# RPi_Extension_load_w_ready.net
KiCad netlist of a schematic drawn in EAGLE
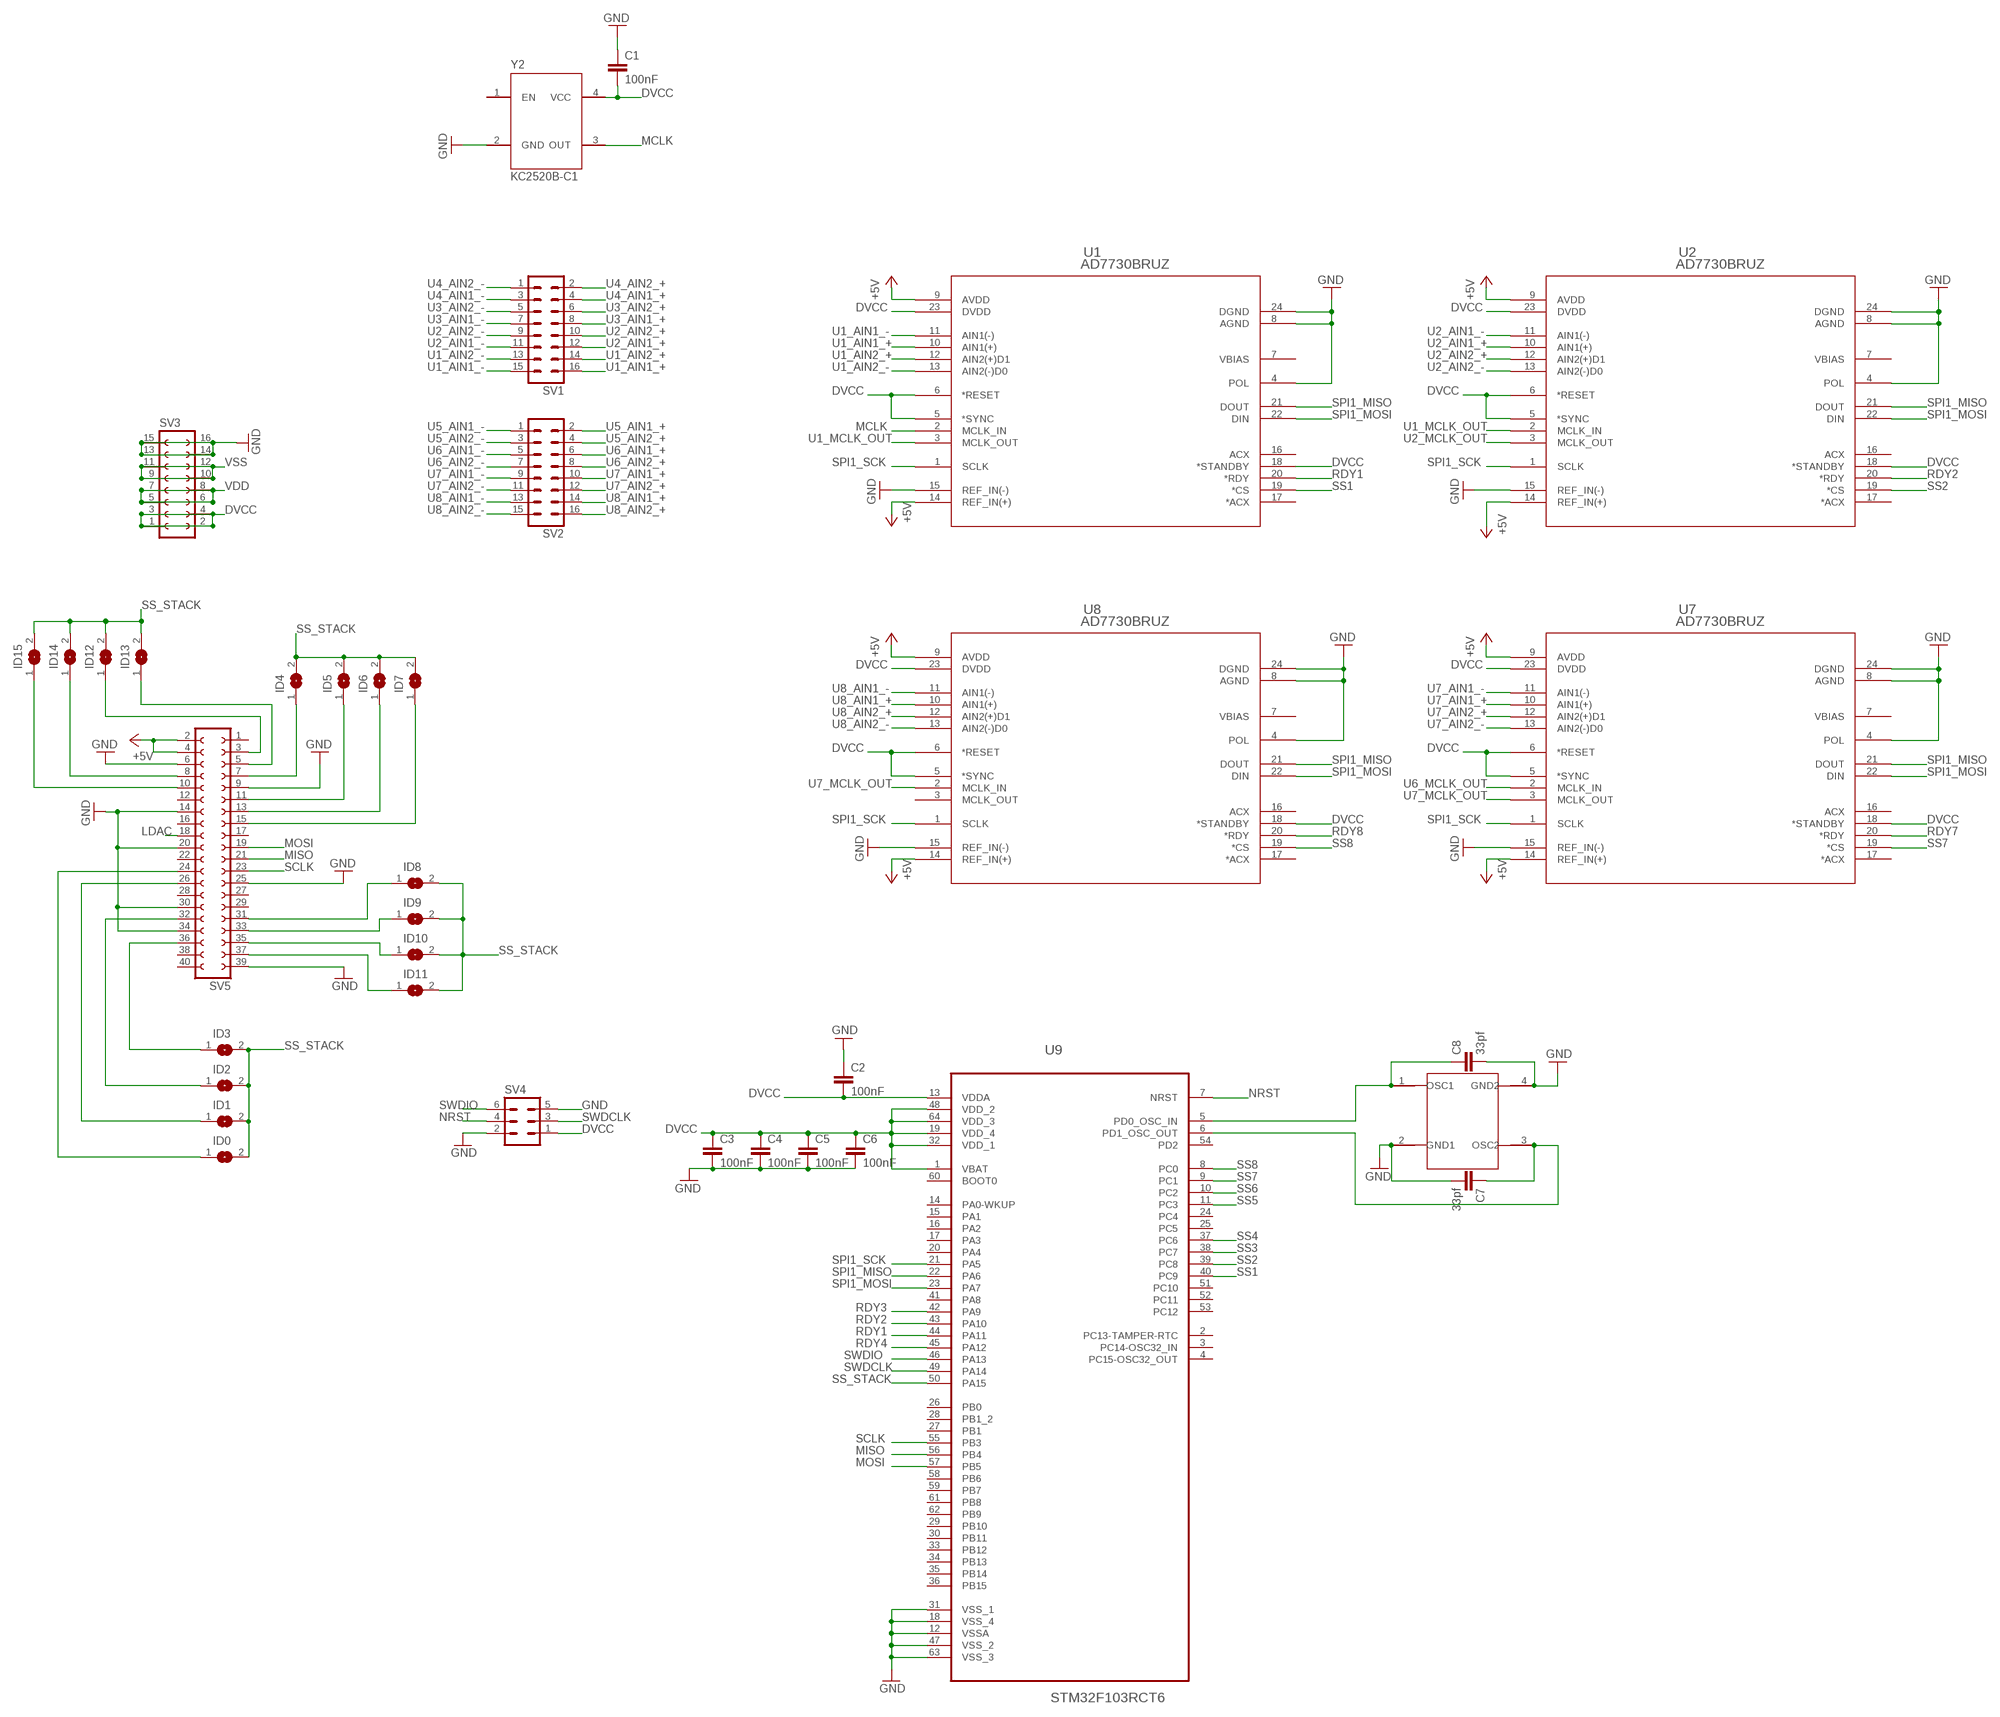
[diagram p0: schematic, sheet 1, part 1 of 2]
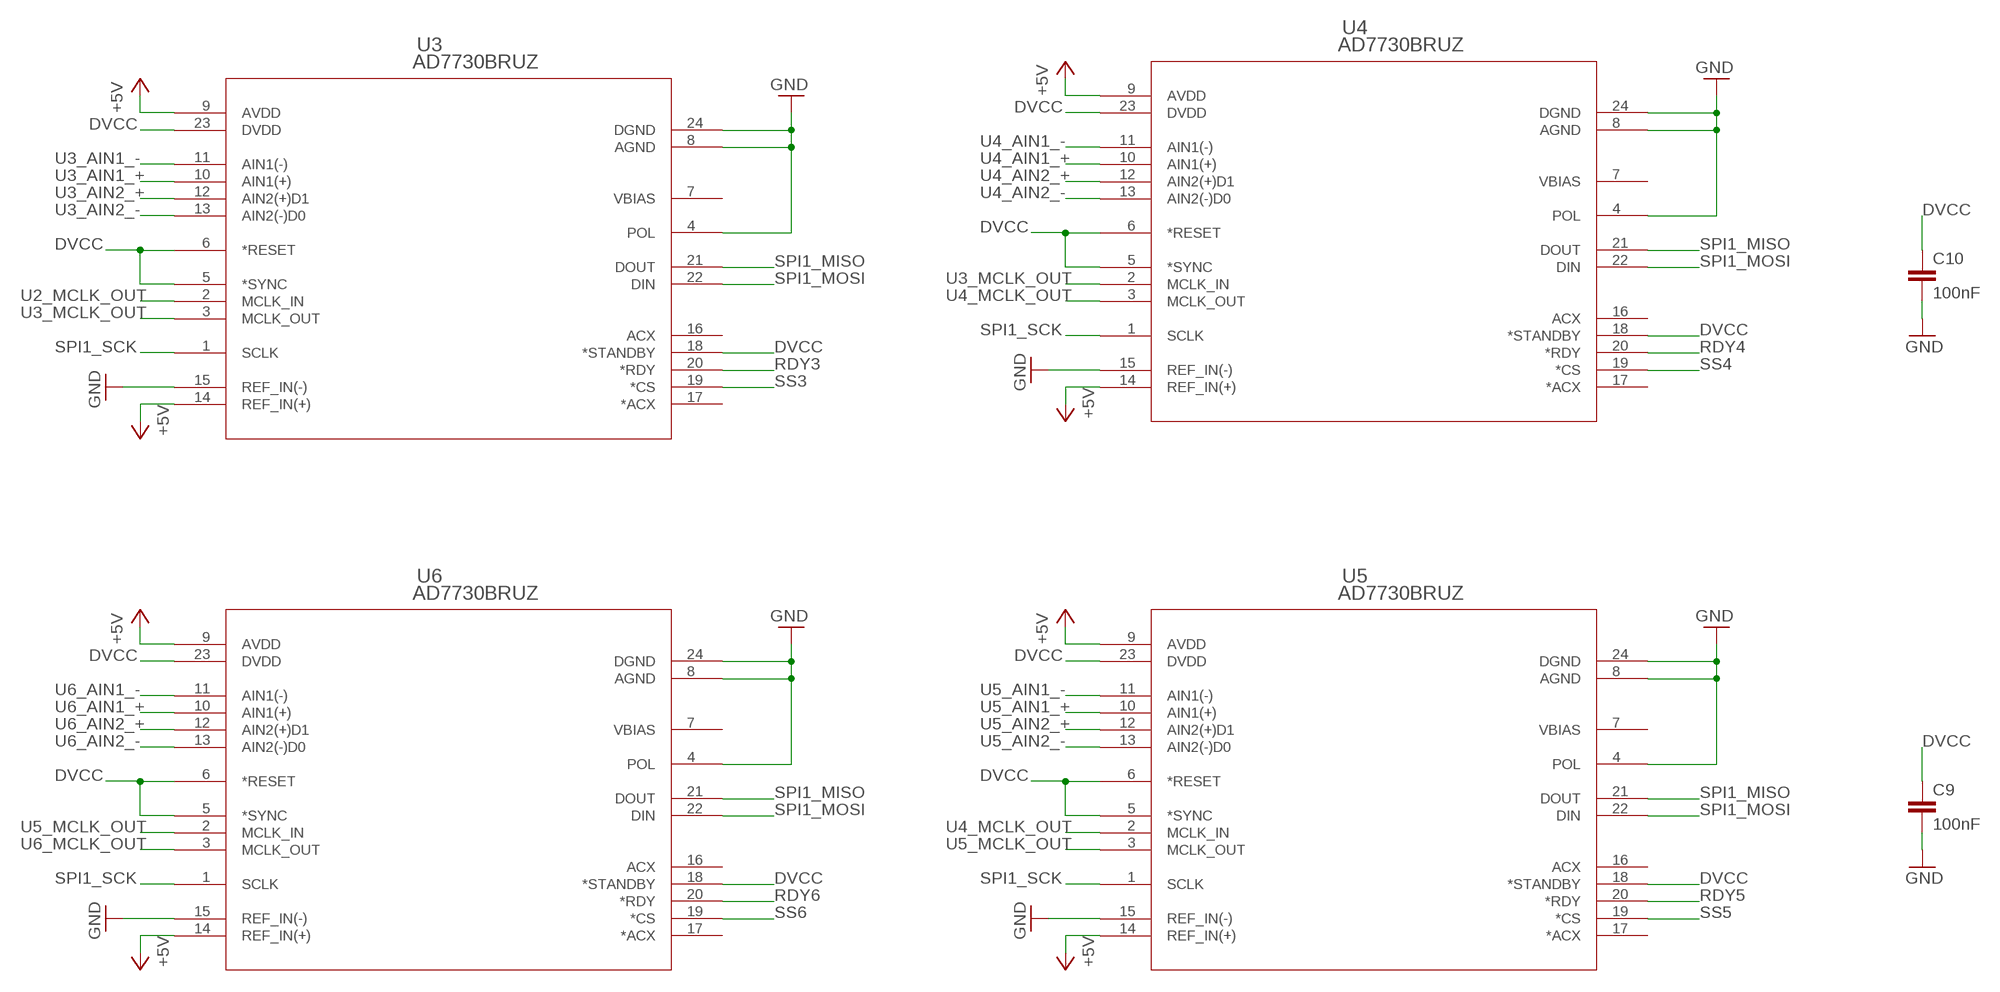
[diagram p1: schematic, sheet 1, part 2 of 2]

(export (version "E")
  (design (tool "Eeschema 10.0.6"))
  (components
    (comp (ref "C1")
      (value "100nF")
      (footprint "eagle-import:C0603")
      (libsource (lib "eagle-import") (part "C-EUC0603"))
    )
    (comp (ref "C2")
      (value "100nF")
      (footprint "eagle-import:C0603")
      (libsource (lib "eagle-import") (part "C-EUC0603"))
    )
    (comp (ref "C3")
      (value "100nF")
      (footprint "eagle-import:C0603")
      (libsource (lib "eagle-import") (part "C-EUC0603"))
    )
    (comp (ref "C4")
      (value "100nF")
      (footprint "eagle-import:C0603")
      (libsource (lib "eagle-import") (part "C-EUC0603"))
    )
    (comp (ref "C5")
      (value "100nF")
      (footprint "eagle-import:C0603")
      (libsource (lib "eagle-import") (part "C-EUC0603"))
    )
    (comp (ref "C6")
      (value "100nF")
      (footprint "eagle-import:C0603")
      (libsource (lib "eagle-import") (part "C-EUC0603"))
    )
    (comp (ref "C7")
      (value "33pf")
      (footprint "eagle-import:C0603")
      (libsource (lib "eagle-import") (part "C-EUC0603"))
    )
    (comp (ref "C8")
      (value "33pf")
      (footprint "eagle-import:C0603")
      (libsource (lib "eagle-import") (part "C-EUC0603"))
    )
    (comp (ref "C9")
      (value "100nF")
      (footprint "eagle-import:C0603")
      (libsource (lib "eagle-import") (part "C-EUC0603"))
    )
    (comp (ref "C10")
      (value "100nF")
      (footprint "eagle-import:C0603")
      (libsource (lib "eagle-import") (part "C-EUC0603"))
    )
    (comp (ref "ID0") (value "SJ") (footprint "eagle-import:SJ") (libsource (lib "eagle-import") (part "SJ")))
    (comp (ref "ID1") (value "SJ") (footprint "eagle-import:SJ") (libsource (lib "eagle-import") (part "SJ")))
    (comp (ref "ID2") (value "SJ") (footprint "eagle-import:SJ") (libsource (lib "eagle-import") (part "SJ")))
    (comp (ref "ID3") (value "SJ") (footprint "eagle-import:SJ") (libsource (lib "eagle-import") (part "SJ")))
    (comp (ref "ID4") (value "SJ") (footprint "eagle-import:SJ") (libsource (lib "eagle-import") (part "SJ")))
    (comp (ref "ID5") (value "SJ") (footprint "eagle-import:SJ") (libsource (lib "eagle-import") (part "SJ")))
    (comp (ref "ID6") (value "SJ") (footprint "eagle-import:SJ") (libsource (lib "eagle-import") (part "SJ")))
    (comp (ref "ID7") (value "SJ") (footprint "eagle-import:SJ") (libsource (lib "eagle-import") (part "SJ")))
    (comp (ref "ID8") (value "SJ") (footprint "eagle-import:SJ") (libsource (lib "eagle-import") (part "SJ")))
    (comp (ref "ID9") (value "SJ") (footprint "eagle-import:SJ") (libsource (lib "eagle-import") (part "SJ")))
    (comp (ref "ID10")
      (value "SJ")
      (footprint "eagle-import:SJ")
      (libsource (lib "eagle-import") (part "SJ"))
    )
    (comp (ref "ID11")
      (value "SJ")
      (footprint "eagle-import:SJ")
      (libsource (lib "eagle-import") (part "SJ"))
    )
    (comp (ref "ID12")
      (value "SJ")
      (footprint "eagle-import:SJ")
      (libsource (lib "eagle-import") (part "SJ"))
    )
    (comp (ref "ID13")
      (value "SJ")
      (footprint "eagle-import:SJ")
      (libsource (lib "eagle-import") (part "SJ"))
    )
    (comp (ref "ID14")
      (value "SJ")
      (footprint "eagle-import:SJ")
      (libsource (lib "eagle-import") (part "SJ"))
    )
    (comp (ref "ID15")
      (value "SJ")
      (footprint "eagle-import:SJ")
      (libsource (lib "eagle-import") (part "SJ"))
    )
    (comp (ref "SV1")
      (value "MA08-2W")
      (footprint "eagle-import:MA08-2W")
      (libsource (lib "eagle-import") (part "MA08-2W"))
    )
    (comp (ref "SV2")
      (value "MA08-2W")
      (footprint "eagle-import:MA08-2W")
      (libsource (lib "eagle-import") (part "MA08-2W"))
    )
    (comp (ref "SV3")
      (value "FE08-2")
      (footprint "eagle-import:FE08-2")
      (libsource (lib "eagle-import") (part "FE08-2"))
    )
    (comp (ref "SV4")
      (value "MA03-2")
      (footprint "eagle-import:MA03-2")
      (libsource (lib "eagle-import") (part "MA03-2"))
    )
    (comp (ref "SV5")
      (value "FE20-2")
      (footprint "eagle-import:FE20-2")
      (libsource (lib "eagle-import") (part "FE20-2"))
    )
    (comp (ref "U1")
      (value "AD7730BRUZ")
      (footprint "eagle-import:RU_24")
      (libsource (lib "eagle-import") (part "AD7730BRUZ"))
    )
    (comp (ref "U2")
      (value "AD7730BRUZ")
      (footprint "eagle-import:RU_24")
      (libsource (lib "eagle-import") (part "AD7730BRUZ"))
    )
    (comp (ref "U3")
      (value "AD7730BRUZ")
      (footprint "eagle-import:RU_24")
      (libsource (lib "eagle-import") (part "AD7730BRUZ"))
    )
    (comp (ref "U4")
      (value "AD7730BRUZ")
      (footprint "eagle-import:RU_24")
      (libsource (lib "eagle-import") (part "AD7730BRUZ"))
    )
    (comp (ref "U5")
      (value "AD7730BRUZ")
      (footprint "eagle-import:RU_24")
      (libsource (lib "eagle-import") (part "AD7730BRUZ"))
    )
    (comp (ref "U6")
      (value "AD7730BRUZ")
      (footprint "eagle-import:RU_24")
      (libsource (lib "eagle-import") (part "AD7730BRUZ"))
    )
    (comp (ref "U7")
      (value "AD7730BRUZ")
      (footprint "eagle-import:RU_24")
      (libsource (lib "eagle-import") (part "AD7730BRUZ"))
    )
    (comp (ref "U8")
      (value "AD7730BRUZ")
      (footprint "eagle-import:RU_24")
      (libsource (lib "eagle-import") (part "AD7730BRUZ"))
    )
    (comp (ref "U9")
      (value "STM32F103RCT6")
      (footprint "eagle-import:QFP50P1200X1200X160-64N")
      (libsource (lib "eagle-import") (part "STM32F103RCT6"))
    )
    (comp (ref "Y1")
      (value "ABM3B")
      (footprint "eagle-import:ABM3B")
      (libsource (lib "eagle-import") (part "ABM3B"))
    )
    (comp (ref "Y2")
      (value "KC2520B-C1")
      (footprint "eagle-import:KC2520B-C1")
      (libsource (lib "eagle-import") (part "KC2520B-C1"))
    )
  )
  (nets
    (net (code "1") (name "+5V") (class "Default")
      (node (ref "SV5") (pin "2") (pinfunction "2_2") (pintype "passive"))
      (node (ref "SV5") (pin "4") (pinfunction "4_4") (pintype "passive"))
      (node (ref "U1") (pin "14") (pinfunction "REF_IN(+)_14") (pintype "passive"))
      (node (ref "U1") (pin "9") (pinfunction "AVDD_9") (pintype "passive"))
      (node (ref "U2") (pin "14") (pinfunction "REF_IN(+)_14") (pintype "passive"))
      (node (ref "U2") (pin "9") (pinfunction "AVDD_9") (pintype "passive"))
      (node (ref "U3") (pin "14") (pinfunction "REF_IN(+)_14") (pintype "passive"))
      (node (ref "U3") (pin "9") (pinfunction "AVDD_9") (pintype "passive"))
      (node (ref "U4") (pin "14") (pinfunction "REF_IN(+)_14") (pintype "passive"))
      (node (ref "U4") (pin "9") (pinfunction "AVDD_9") (pintype "passive"))
      (node (ref "U5") (pin "14") (pinfunction "REF_IN(+)_14") (pintype "passive"))
      (node (ref "U5") (pin "9") (pinfunction "AVDD_9") (pintype "passive"))
      (node (ref "U6") (pin "14") (pinfunction "REF_IN(+)_14") (pintype "passive"))
      (node (ref "U6") (pin "9") (pinfunction "AVDD_9") (pintype "passive"))
      (node (ref "U7") (pin "14") (pinfunction "REF_IN(+)_14") (pintype "passive"))
      (node (ref "U7") (pin "9") (pinfunction "AVDD_9") (pintype "passive"))
      (node (ref "U8") (pin "14") (pinfunction "REF_IN(+)_14") (pintype "passive"))
      (node (ref "U8") (pin "9") (pinfunction "AVDD_9") (pintype "passive"))
    )
    (net (code "2") (name "/DVCC") (class "Default")
      (node (ref "C1") (pin "2") (pinfunction "2_2") (pintype "passive"))
      (node (ref "C10") (pin "1") (pinfunction "1_1") (pintype "passive"))
      (node (ref "C2") (pin "2") (pinfunction "2_2") (pintype "passive"))
      (node (ref "C3") (pin "1") (pinfunction "1_1") (pintype "passive"))
      (node (ref "C4") (pin "1") (pinfunction "1_1") (pintype "passive"))
      (node (ref "C5") (pin "1") (pinfunction "1_1") (pintype "passive"))
      (node (ref "C6") (pin "1") (pinfunction "1_1") (pintype "passive"))
      (node (ref "C9") (pin "1") (pinfunction "1_1") (pintype "passive"))
      (node (ref "SV3") (pin "1") (pinfunction "1_1") (pintype "passive"))
      (node (ref "SV3") (pin "2") (pinfunction "2_2") (pintype "passive"))
      (node (ref "SV3") (pin "3") (pinfunction "3_3") (pintype "passive"))
      (node (ref "SV3") (pin "4") (pinfunction "4_4") (pintype "passive"))
      (node (ref "SV4") (pin "1") (pinfunction "1_1") (pintype "passive"))
      (node (ref "U1") (pin "18") (pinfunction "*STANDBY_18") (pintype "passive"))
      (node (ref "U1") (pin "23") (pinfunction "DVDD_23") (pintype "passive"))
      (node (ref "U1") (pin "5") (pinfunction "*SYNC_5") (pintype "passive"))
      (node (ref "U1") (pin "6") (pinfunction "*RESET_6") (pintype "passive"))
      (node (ref "U2") (pin "18") (pinfunction "*STANDBY_18") (pintype "passive"))
      (node (ref "U2") (pin "23") (pinfunction "DVDD_23") (pintype "passive"))
      (node (ref "U2") (pin "5") (pinfunction "*SYNC_5") (pintype "passive"))
      (node (ref "U2") (pin "6") (pinfunction "*RESET_6") (pintype "passive"))
      (node (ref "U3") (pin "18") (pinfunction "*STANDBY_18") (pintype "passive"))
      (node (ref "U3") (pin "23") (pinfunction "DVDD_23") (pintype "passive"))
      (node (ref "U3") (pin "5") (pinfunction "*SYNC_5") (pintype "passive"))
      (node (ref "U3") (pin "6") (pinfunction "*RESET_6") (pintype "passive"))
      (node (ref "U4") (pin "18") (pinfunction "*STANDBY_18") (pintype "passive"))
      (node (ref "U4") (pin "23") (pinfunction "DVDD_23") (pintype "passive"))
      (node (ref "U4") (pin "5") (pinfunction "*SYNC_5") (pintype "passive"))
      (node (ref "U4") (pin "6") (pinfunction "*RESET_6") (pintype "passive"))
      (node (ref "U5") (pin "18") (pinfunction "*STANDBY_18") (pintype "passive"))
      (node (ref "U5") (pin "23") (pinfunction "DVDD_23") (pintype "passive"))
      (node (ref "U5") (pin "5") (pinfunction "*SYNC_5") (pintype "passive"))
      (node (ref "U5") (pin "6") (pinfunction "*RESET_6") (pintype "passive"))
      (node (ref "U6") (pin "18") (pinfunction "*STANDBY_18") (pintype "passive"))
      (node (ref "U6") (pin "23") (pinfunction "DVDD_23") (pintype "passive"))
      (node (ref "U6") (pin "5") (pinfunction "*SYNC_5") (pintype "passive"))
      (node (ref "U6") (pin "6") (pinfunction "*RESET_6") (pintype "passive"))
      (node (ref "U7") (pin "18") (pinfunction "*STANDBY_18") (pintype "passive"))
      (node (ref "U7") (pin "23") (pinfunction "DVDD_23") (pintype "passive"))
      (node (ref "U7") (pin "5") (pinfunction "*SYNC_5") (pintype "passive"))
      (node (ref "U7") (pin "6") (pinfunction "*RESET_6") (pintype "passive"))
      (node (ref "U8") (pin "18") (pinfunction "*STANDBY_18") (pintype "passive"))
      (node (ref "U8") (pin "23") (pinfunction "DVDD_23") (pintype "passive"))
      (node (ref "U8") (pin "5") (pinfunction "*SYNC_5") (pintype "passive"))
      (node (ref "U8") (pin "6") (pinfunction "*RESET_6") (pintype "passive"))
      (node (ref "U9") (pin "1") (pinfunction "VBAT_1") (pintype "input"))
      (node (ref "U9") (pin "13") (pinfunction "VDDA_13") (pintype "power_in"))
      (node (ref "U9") (pin "19") (pinfunction "VDD_4_19") (pintype "power_in"))
      (node (ref "U9") (pin "32") (pinfunction "VDD_1_32") (pintype "power_in"))
      (node (ref "U9") (pin "48") (pinfunction "VDD_2_48") (pintype "power_in"))
      (node (ref "U9") (pin "64") (pinfunction "VDD_3_64") (pintype "power_in"))
      (node (ref "Y2") (pin "4") (pinfunction "VCC_4") (pintype "bidirectional"))
    )
    (net (code "3") (name "/LDAC") (class "Default")
      (node (ref "SV5") (pin "18") (pinfunction "18_18") (pintype "passive"))
    )
    (net (code "4") (name "/MCLK") (class "Default")
      (node (ref "U1") (pin "2") (pinfunction "MCLK_IN_2") (pintype "passive"))
      (node (ref "Y2") (pin "3") (pinfunction "OUT_3") (pintype "bidirectional"))
    )
    (net (code "5") (name "/MISO") (class "Default")
      (node (ref "SV5") (pin "21") (pinfunction "21_21") (pintype "passive"))
      (node (ref "U9") (pin "56") (pinfunction "PB4_56") (pintype "bidirectional"))
    )
    (net (code "6") (name "/MOSI") (class "Default")
      (node (ref "SV5") (pin "19") (pinfunction "19_19") (pintype "passive"))
      (node (ref "U9") (pin "57") (pinfunction "PB5_57") (pintype "bidirectional"))
    )
    (net (code "7") (name "/NRST") (class "Default")
      (node (ref "SV4") (pin "4") (pinfunction "4_4") (pintype "passive"))
      (node (ref "U9") (pin "7") (pinfunction "NRST_7") (pintype "output"))
    )
    (net (code "8") (name "/PB7") (class "Default")
      (node (ref "U9") (pin "59") (pinfunction "PB7_59") (pintype "power_in"))
    )
    (net (code "9") (name "/RDY1") (class "Default")
      (node (ref "U1") (pin "20") (pinfunction "*RDY_20") (pintype "passive"))
      (node (ref "U9") (pin "44") (pinfunction "PA11_44") (pintype "bidirectional"))
    )
    (net (code "10") (name "/RDY2") (class "Default")
      (node (ref "U2") (pin "20") (pinfunction "*RDY_20") (pintype "passive"))
      (node (ref "U9") (pin "43") (pinfunction "PA10_43") (pintype "bidirectional"))
    )
    (net (code "11") (name "/RDY3") (class "Default")
      (node (ref "U3") (pin "20") (pinfunction "*RDY_20") (pintype "passive"))
      (node (ref "U9") (pin "42") (pinfunction "PA9_42") (pintype "bidirectional"))
    )
    (net (code "12") (name "/RDY4") (class "Default")
      (node (ref "U4") (pin "20") (pinfunction "*RDY_20") (pintype "passive"))
      (node (ref "U9") (pin "45") (pinfunction "PA12_45") (pintype "bidirectional"))
    )
    (net (code "13") (name "/RDY5") (class "Default")
      (node (ref "U5") (pin "20") (pinfunction "*RDY_20") (pintype "passive"))
    )
    (net (code "14") (name "/RDY6") (class "Default")
      (node (ref "U6") (pin "20") (pinfunction "*RDY_20") (pintype "passive"))
    )
    (net (code "15") (name "/RDY7") (class "Default")
      (node (ref "U7") (pin "20") (pinfunction "*RDY_20") (pintype "passive"))
    )
    (net (code "16") (name "/RDY8") (class "Default")
      (node (ref "U8") (pin "20") (pinfunction "*RDY_20") (pintype "passive"))
    )
    (net (code "17") (name "/SCLK") (class "Default")
      (node (ref "SV5") (pin "23") (pinfunction "23_23") (pintype "passive"))
      (node (ref "U9") (pin "55") (pinfunction "PB3_55") (pintype "bidirectional"))
    )
    (net (code "18") (name "/SPI1_MISO") (class "Default")
      (node (ref "U1") (pin "21") (pinfunction "DOUT_21") (pintype "passive"))
      (node (ref "U2") (pin "21") (pinfunction "DOUT_21") (pintype "passive"))
      (node (ref "U3") (pin "21") (pinfunction "DOUT_21") (pintype "passive"))
      (node (ref "U4") (pin "21") (pinfunction "DOUT_21") (pintype "passive"))
      (node (ref "U5") (pin "21") (pinfunction "DOUT_21") (pintype "passive"))
      (node (ref "U6") (pin "21") (pinfunction "DOUT_21") (pintype "passive"))
      (node (ref "U7") (pin "21") (pinfunction "DOUT_21") (pintype "passive"))
      (node (ref "U8") (pin "21") (pinfunction "DOUT_21") (pintype "passive"))
      (node (ref "U9") (pin "22") (pinfunction "PA6_22") (pintype "bidirectional"))
    )
    (net (code "19") (name "/SPI1_MOSI") (class "Default")
      (node (ref "U1") (pin "22") (pinfunction "DIN_22") (pintype "passive"))
      (node (ref "U2") (pin "22") (pinfunction "DIN_22") (pintype "passive"))
      (node (ref "U3") (pin "22") (pinfunction "DIN_22") (pintype "passive"))
      (node (ref "U4") (pin "22") (pinfunction "DIN_22") (pintype "passive"))
      (node (ref "U5") (pin "22") (pinfunction "DIN_22") (pintype "passive"))
      (node (ref "U6") (pin "22") (pinfunction "DIN_22") (pintype "passive"))
      (node (ref "U7") (pin "22") (pinfunction "DIN_22") (pintype "passive"))
      (node (ref "U8") (pin "22") (pinfunction "DIN_22") (pintype "passive"))
      (node (ref "U9") (pin "23") (pinfunction "PA7_23") (pintype "power_in"))
    )
    (net (code "20") (name "/SPI1_SCK") (class "Default")
      (node (ref "U1") (pin "1") (pinfunction "SCLK_1") (pintype "passive"))
      (node (ref "U2") (pin "1") (pinfunction "SCLK_1") (pintype "passive"))
      (node (ref "U3") (pin "1") (pinfunction "SCLK_1") (pintype "passive"))
      (node (ref "U4") (pin "1") (pinfunction "SCLK_1") (pintype "passive"))
      (node (ref "U5") (pin "1") (pinfunction "SCLK_1") (pintype "passive"))
      (node (ref "U6") (pin "1") (pinfunction "SCLK_1") (pintype "passive"))
      (node (ref "U7") (pin "1") (pinfunction "SCLK_1") (pintype "passive"))
      (node (ref "U8") (pin "1") (pinfunction "SCLK_1") (pintype "passive"))
      (node (ref "U9") (pin "21") (pinfunction "PA5_21") (pintype "bidirectional"))
    )
    (net (code "21") (name "/SS1") (class "Default")
      (node (ref "U1") (pin "19") (pinfunction "*CS_19") (pintype "passive"))
      (node (ref "U9") (pin "40") (pinfunction "PC9_40") (pintype "bidirectional"))
    )
    (net (code "22") (name "/SS2") (class "Default")
      (node (ref "U2") (pin "19") (pinfunction "*CS_19") (pintype "passive"))
      (node (ref "U9") (pin "39") (pinfunction "PC8_39") (pintype "bidirectional"))
    )
    (net (code "23") (name "/SS3") (class "Default")
      (node (ref "U3") (pin "19") (pinfunction "*CS_19") (pintype "passive"))
      (node (ref "U9") (pin "38") (pinfunction "PC7_38") (pintype "bidirectional"))
    )
    (net (code "24") (name "/SS4") (class "Default")
      (node (ref "U4") (pin "19") (pinfunction "*CS_19") (pintype "passive"))
      (node (ref "U9") (pin "37") (pinfunction "PC6_37") (pintype "bidirectional"))
    )
    (net (code "25") (name "/SS5") (class "Default")
      (node (ref "U5") (pin "19") (pinfunction "*CS_19") (pintype "passive"))
      (node (ref "U9") (pin "11") (pinfunction "PC3_11") (pintype "bidirectional"))
    )
    (net (code "26") (name "/SS6") (class "Default")
      (node (ref "U6") (pin "19") (pinfunction "*CS_19") (pintype "passive"))
      (node (ref "U9") (pin "10") (pinfunction "PC2_10") (pintype "bidirectional"))
    )
    (net (code "27") (name "/SS7") (class "Default")
      (node (ref "U7") (pin "19") (pinfunction "*CS_19") (pintype "passive"))
      (node (ref "U9") (pin "9") (pinfunction "PC1_9") (pintype "bidirectional"))
    )
    (net (code "28") (name "/SS8") (class "Default")
      (node (ref "U8") (pin "19") (pinfunction "*CS_19") (pintype "passive"))
      (node (ref "U9") (pin "8") (pinfunction "PC0_8") (pintype "bidirectional"))
    )
    (net (code "29") (name "/SS_STACK") (class "Default")
      (node (ref "ID0") (pin "2") (pinfunction "2_2") (pintype "passive"))
      (node (ref "ID1") (pin "2") (pinfunction "2_2") (pintype "passive"))
      (node (ref "ID10") (pin "2") (pinfunction "2_2") (pintype "passive"))
      (node (ref "ID11") (pin "2") (pinfunction "2_2") (pintype "passive"))
      (node (ref "ID12") (pin "2") (pinfunction "2_2") (pintype "passive"))
      (node (ref "ID13") (pin "2") (pinfunction "2_2") (pintype "passive"))
      (node (ref "ID14") (pin "2") (pinfunction "2_2") (pintype "passive"))
      (node (ref "ID15") (pin "2") (pinfunction "2_2") (pintype "passive"))
      (node (ref "ID2") (pin "2") (pinfunction "2_2") (pintype "passive"))
      (node (ref "ID3") (pin "2") (pinfunction "2_2") (pintype "passive"))
      (node (ref "ID4") (pin "2") (pinfunction "2_2") (pintype "passive"))
      (node (ref "ID5") (pin "2") (pinfunction "2_2") (pintype "passive"))
      (node (ref "ID6") (pin "2") (pinfunction "2_2") (pintype "passive"))
      (node (ref "ID7") (pin "2") (pinfunction "2_2") (pintype "passive"))
      (node (ref "ID8") (pin "2") (pinfunction "2_2") (pintype "passive"))
      (node (ref "ID9") (pin "2") (pinfunction "2_2") (pintype "passive"))
      (node (ref "U9") (pin "50") (pinfunction "PA15_50") (pintype "bidirectional"))
    )
    (net (code "30") (name "/SWDCLK") (class "Default")
      (node (ref "SV4") (pin "3") (pinfunction "3_3") (pintype "passive"))
      (node (ref "U9") (pin "49") (pinfunction "PA14_49") (pintype "bidirectional"))
    )
    (net (code "31") (name "/SWDIO") (class "Default")
      (node (ref "SV4") (pin "6") (pinfunction "6_6") (pintype "passive"))
      (node (ref "U9") (pin "46") (pinfunction "PA13_46") (pintype "bidirectional"))
    )
    (net (code "32") (name "/U1_AIN1_+") (class "Default")
      (node (ref "SV1") (pin "16") (pinfunction "16_16") (pintype "passive"))
      (node (ref "U1") (pin "10") (pinfunction "AIN1(+)_10") (pintype "passive"))
    )
    (net (code "33") (name "/U1_AIN1_-") (class "Default")
      (node (ref "SV1") (pin "15") (pinfunction "15_15") (pintype "passive"))
      (node (ref "U1") (pin "11") (pinfunction "AIN1(-)_11") (pintype "passive"))
    )
    (net (code "34") (name "/U1_AIN2_+") (class "Default")
      (node (ref "SV1") (pin "14") (pinfunction "14_14") (pintype "passive"))
      (node (ref "U1") (pin "12") (pinfunction "AIN2(+)D1_12") (pintype "passive"))
    )
    (net (code "35") (name "/U1_AIN2_-") (class "Default")
      (node (ref "SV1") (pin "13") (pinfunction "13_13") (pintype "passive"))
      (node (ref "U1") (pin "13") (pinfunction "AIN2(-)D0_13") (pintype "passive"))
    )
    (net (code "36") (name "/U1_MCLK_OUT") (class "Default")
      (node (ref "U1") (pin "3") (pinfunction "MCLK_OUT_3") (pintype "passive"))
      (node (ref "U2") (pin "2") (pinfunction "MCLK_IN_2") (pintype "passive"))
    )
    (net (code "37") (name "/U2_AIN1_+") (class "Default")
      (node (ref "SV1") (pin "12") (pinfunction "12_12") (pintype "passive"))
      (node (ref "U2") (pin "10") (pinfunction "AIN1(+)_10") (pintype "passive"))
    )
    (net (code "38") (name "/U2_AIN1_-") (class "Default")
      (node (ref "SV1") (pin "11") (pinfunction "11_11") (pintype "passive"))
      (node (ref "U2") (pin "11") (pinfunction "AIN1(-)_11") (pintype "passive"))
    )
    (net (code "39") (name "/U2_AIN2_+") (class "Default")
      (node (ref "SV1") (pin "10") (pinfunction "10_10") (pintype "passive"))
      (node (ref "U2") (pin "12") (pinfunction "AIN2(+)D1_12") (pintype "passive"))
    )
    (net (code "40") (name "/U2_AIN2_-") (class "Default")
      (node (ref "SV1") (pin "9") (pinfunction "9_9") (pintype "passive"))
      (node (ref "U2") (pin "13") (pinfunction "AIN2(-)D0_13") (pintype "passive"))
    )
    (net (code "41") (name "/U2_MCLK_OUT") (class "Default")
      (node (ref "U2") (pin "3") (pinfunction "MCLK_OUT_3") (pintype "passive"))
      (node (ref "U3") (pin "2") (pinfunction "MCLK_IN_2") (pintype "passive"))
    )
    (net (code "42") (name "/U3_AIN1_+") (class "Default")
      (node (ref "SV1") (pin "8") (pinfunction "8_8") (pintype "passive"))
      (node (ref "U3") (pin "10") (pinfunction "AIN1(+)_10") (pintype "passive"))
    )
    (net (code "43") (name "/U3_AIN1_-") (class "Default")
      (node (ref "SV1") (pin "7") (pinfunction "7_7") (pintype "passive"))
      (node (ref "U3") (pin "11") (pinfunction "AIN1(-)_11") (pintype "passive"))
    )
    (net (code "44") (name "/U3_AIN2_+") (class "Default")
      (node (ref "SV1") (pin "6") (pinfunction "6_6") (pintype "passive"))
      (node (ref "U3") (pin "12") (pinfunction "AIN2(+)D1_12") (pintype "passive"))
    )
    (net (code "45") (name "/U3_AIN2_-") (class "Default")
      (node (ref "SV1") (pin "5") (pinfunction "5_5") (pintype "passive"))
      (node (ref "U3") (pin "13") (pinfunction "AIN2(-)D0_13") (pintype "passive"))
    )
    (net (code "46") (name "/U3_MCLK_OUT") (class "Default")
      (node (ref "U3") (pin "3") (pinfunction "MCLK_OUT_3") (pintype "passive"))
      (node (ref "U4") (pin "2") (pinfunction "MCLK_IN_2") (pintype "passive"))
    )
    (net (code "47") (name "/U4_AIN1_+") (class "Default")
      (node (ref "SV1") (pin "4") (pinfunction "4_4") (pintype "passive"))
      (node (ref "U4") (pin "10") (pinfunction "AIN1(+)_10") (pintype "passive"))
    )
    (net (code "48") (name "/U4_AIN1_-") (class "Default")
      (node (ref "SV1") (pin "3") (pinfunction "3_3") (pintype "passive"))
      (node (ref "U4") (pin "11") (pinfunction "AIN1(-)_11") (pintype "passive"))
    )
    (net (code "49") (name "/U4_AIN2_+") (class "Default")
      (node (ref "SV1") (pin "2") (pinfunction "2_2") (pintype "passive"))
      (node (ref "U4") (pin "12") (pinfunction "AIN2(+)D1_12") (pintype "passive"))
    )
    (net (code "50") (name "/U4_AIN2_-") (class "Default")
      (node (ref "SV1") (pin "1") (pinfunction "1_1") (pintype "passive"))
      (node (ref "U4") (pin "13") (pinfunction "AIN2(-)D0_13") (pintype "passive"))
    )
    (net (code "51") (name "/U4_MCLK_OUT") (class "Default")
      (node (ref "U4") (pin "3") (pinfunction "MCLK_OUT_3") (pintype "passive"))
      (node (ref "U5") (pin "2") (pinfunction "MCLK_IN_2") (pintype "passive"))
    )
    (net (code "52") (name "/U5_AIN1_+") (class "Default")
      (node (ref "SV2") (pin "2") (pinfunction "2_2") (pintype "passive"))
      (node (ref "U5") (pin "10") (pinfunction "AIN1(+)_10") (pintype "passive"))
    )
    (net (code "53") (name "/U5_AIN1_-") (class "Default")
      (node (ref "SV2") (pin "1") (pinfunction "1_1") (pintype "passive"))
      (node (ref "U5") (pin "11") (pinfunction "AIN1(-)_11") (pintype "passive"))
    )
    (net (code "54") (name "/U5_AIN2_+") (class "Default")
      (node (ref "SV2") (pin "4") (pinfunction "4_4") (pintype "passive"))
      (node (ref "U5") (pin "12") (pinfunction "AIN2(+)D1_12") (pintype "passive"))
    )
    (net (code "55") (name "/U5_AIN2_-") (class "Default")
      (node (ref "SV2") (pin "3") (pinfunction "3_3") (pintype "passive"))
      (node (ref "U5") (pin "13") (pinfunction "AIN2(-)D0_13") (pintype "passive"))
    )
    (net (code "56") (name "/U5_MCLK_OUT") (class "Default")
      (node (ref "U5") (pin "3") (pinfunction "MCLK_OUT_3") (pintype "passive"))
      (node (ref "U6") (pin "2") (pinfunction "MCLK_IN_2") (pintype "passive"))
    )
    (net (code "57") (name "/U6_AIN1_+") (class "Default")
      (node (ref "SV2") (pin "6") (pinfunction "6_6") (pintype "passive"))
      (node (ref "U6") (pin "10") (pinfunction "AIN1(+)_10") (pintype "passive"))
    )
    (net (code "58") (name "/U6_AIN1_-") (class "Default")
      (node (ref "SV2") (pin "5") (pinfunction "5_5") (pintype "passive"))
      (node (ref "U6") (pin "11") (pinfunction "AIN1(-)_11") (pintype "passive"))
    )
    (net (code "59") (name "/U6_AIN2_+") (class "Default")
      (node (ref "SV2") (pin "8") (pinfunction "8_8") (pintype "passive"))
      (node (ref "U6") (pin "12") (pinfunction "AIN2(+)D1_12") (pintype "passive"))
    )
    (net (code "60") (name "/U6_AIN2_-") (class "Default")
      (node (ref "SV2") (pin "7") (pinfunction "7_7") (pintype "passive"))
      (node (ref "U6") (pin "13") (pinfunction "AIN2(-)D0_13") (pintype "passive"))
    )
    (net (code "61") (name "/U6_MCLK_OUT") (class "Default")
      (node (ref "U6") (pin "3") (pinfunction "MCLK_OUT_3") (pintype "passive"))
      (node (ref "U7") (pin "2") (pinfunction "MCLK_IN_2") (pintype "passive"))
    )
    (net (code "62") (name "/U7_AIN1_+") (class "Default")
      (node (ref "SV2") (pin "10") (pinfunction "10_10") (pintype "passive"))
      (node (ref "U7") (pin "10") (pinfunction "AIN1(+)_10") (pintype "passive"))
    )
    (net (code "63") (name "/U7_AIN1_-") (class "Default")
      (node (ref "SV2") (pin "9") (pinfunction "9_9") (pintype "passive"))
      (node (ref "U7") (pin "11") (pinfunction "AIN1(-)_11") (pintype "passive"))
    )
    (net (code "64") (name "/U7_AIN2_+") (class "Default")
      (node (ref "SV2") (pin "12") (pinfunction "12_12") (pintype "passive"))
      (node (ref "U7") (pin "12") (pinfunction "AIN2(+)D1_12") (pintype "passive"))
    )
    (net (code "65") (name "/U7_AIN2_-") (class "Default")
      (node (ref "SV2") (pin "11") (pinfunction "11_11") (pintype "passive"))
      (node (ref "U7") (pin "13") (pinfunction "AIN2(-)D0_13") (pintype "passive"))
    )
    (net (code "66") (name "/U7_MCLK_OUT") (class "Default")
      (node (ref "U7") (pin "3") (pinfunction "MCLK_OUT_3") (pintype "passive"))
      (node (ref "U8") (pin "2") (pinfunction "MCLK_IN_2") (pintype "passive"))
    )
    (net (code "67") (name "/U8_AIN1_+") (class "Default")
      (node (ref "SV2") (pin "14") (pinfunction "14_14") (pintype "passive"))
      (node (ref "U8") (pin "10") (pinfunction "AIN1(+)_10") (pintype "passive"))
    )
    (net (code "68") (name "/U8_AIN1_-") (class "Default")
      (node (ref "SV2") (pin "13") (pinfunction "13_13") (pintype "passive"))
      (node (ref "U8") (pin "11") (pinfunction "AIN1(-)_11") (pintype "passive"))
    )
    (net (code "69") (name "/U8_AIN2_+") (class "Default")
      (node (ref "SV2") (pin "16") (pinfunction "16_16") (pintype "passive"))
      (node (ref "U8") (pin "12") (pinfunction "AIN2(+)D1_12") (pintype "passive"))
    )
    (net (code "70") (name "/U8_AIN2_-") (class "Default")
      (node (ref "SV2") (pin "15") (pinfunction "15_15") (pintype "passive"))
      (node (ref "U8") (pin "13") (pinfunction "AIN2(-)D0_13") (pintype "passive"))
    )
    (net (code "71") (name "/VDD") (class "Default")
      (node (ref "SV3") (pin "5") (pinfunction "5_5") (pintype "passive"))
      (node (ref "SV3") (pin "6") (pinfunction "6_6") (pintype "passive"))
      (node (ref "SV3") (pin "7") (pinfunction "7_7") (pintype "passive"))
      (node (ref "SV3") (pin "8") (pinfunction "8_8") (pintype "passive"))
    )
    (net (code "72") (name "/VSS") (class "Default")
      (node (ref "SV3") (pin "10") (pinfunction "10_10") (pintype "passive"))
      (node (ref "SV3") (pin "11") (pinfunction "11_11") (pintype "passive"))
      (node (ref "SV3") (pin "12") (pinfunction "12_12") (pintype "passive"))
      (node (ref "SV3") (pin "9") (pinfunction "9_9") (pintype "passive"))
    )
    (net (code "73") (name "GND") (class "Default")
      (node (ref "C1") (pin "1") (pinfunction "1_1") (pintype "passive"))
      (node (ref "C10") (pin "2") (pinfunction "2_2") (pintype "passive"))
      (node (ref "C2") (pin "1") (pinfunction "1_1") (pintype "passive"))
      (node (ref "C3") (pin "2") (pinfunction "2_2") (pintype "passive"))
      (node (ref "C4") (pin "2") (pinfunction "2_2") (pintype "passive"))
      (node (ref "C5") (pin "2") (pinfunction "2_2") (pintype "passive"))
      (node (ref "C6") (pin "2") (pinfunction "2_2") (pintype "passive"))
      (node (ref "C7") (pin "2") (pinfunction "2_2") (pintype "passive"))
      (node (ref "C8") (pin "2") (pinfunction "2_2") (pintype "passive"))
      (node (ref "C9") (pin "2") (pinfunction "2_2") (pintype "passive"))
      (node (ref "SV3") (pin "13") (pinfunction "13_13") (pintype "passive"))
      (node (ref "SV3") (pin "14") (pinfunction "14_14") (pintype "passive"))
      (node (ref "SV3") (pin "15") (pinfunction "15_15") (pintype "passive"))
      (node (ref "SV3") (pin "16") (pinfunction "16_16") (pintype "passive"))
      (node (ref "SV4") (pin "2") (pinfunction "2_2") (pintype "passive"))
      (node (ref "SV4") (pin "5") (pinfunction "5_5") (pintype "passive"))
      (node (ref "SV5") (pin "14") (pinfunction "14_14") (pintype "passive"))
      (node (ref "SV5") (pin "20") (pinfunction "20_20") (pintype "passive"))
      (node (ref "SV5") (pin "25") (pinfunction "25_25") (pintype "passive"))
      (node (ref "SV5") (pin "30") (pinfunction "30_30") (pintype "passive"))
      (node (ref "SV5") (pin "34") (pinfunction "34_34") (pintype "passive"))
      (node (ref "SV5") (pin "39") (pinfunction "39_39") (pintype "passive"))
      (node (ref "SV5") (pin "6") (pinfunction "6_6") (pintype "passive"))
      (node (ref "SV5") (pin "9") (pinfunction "9_9") (pintype "passive"))
      (node (ref "U1") (pin "15") (pinfunction "REF_IN(-)_15") (pintype "passive"))
      (node (ref "U1") (pin "24") (pinfunction "DGND_24") (pintype "passive"))
      (node (ref "U1") (pin "4") (pinfunction "POL_4") (pintype "passive"))
      (node (ref "U1") (pin "8") (pinfunction "AGND_8") (pintype "passive"))
      (node (ref "U2") (pin "15") (pinfunction "REF_IN(-)_15") (pintype "passive"))
      (node (ref "U2") (pin "24") (pinfunction "DGND_24") (pintype "passive"))
      (node (ref "U2") (pin "4") (pinfunction "POL_4") (pintype "passive"))
      (node (ref "U2") (pin "8") (pinfunction "AGND_8") (pintype "passive"))
      (node (ref "U3") (pin "15") (pinfunction "REF_IN(-)_15") (pintype "passive"))
      (node (ref "U3") (pin "24") (pinfunction "DGND_24") (pintype "passive"))
      (node (ref "U3") (pin "4") (pinfunction "POL_4") (pintype "passive"))
      (node (ref "U3") (pin "8") (pinfunction "AGND_8") (pintype "passive"))
      (node (ref "U4") (pin "15") (pinfunction "REF_IN(-)_15") (pintype "passive"))
      (node (ref "U4") (pin "24") (pinfunction "DGND_24") (pintype "passive"))
      (node (ref "U4") (pin "4") (pinfunction "POL_4") (pintype "passive"))
      (node (ref "U4") (pin "8") (pinfunction "AGND_8") (pintype "passive"))
      (node (ref "U5") (pin "15") (pinfunction "REF_IN(-)_15") (pintype "passive"))
      (node (ref "U5") (pin "24") (pinfunction "DGND_24") (pintype "passive"))
      (node (ref "U5") (pin "4") (pinfunction "POL_4") (pintype "passive"))
      (node (ref "U5") (pin "8") (pinfunction "AGND_8") (pintype "passive"))
      (node (ref "U6") (pin "15") (pinfunction "REF_IN(-)_15") (pintype "passive"))
      (node (ref "U6") (pin "24") (pinfunction "DGND_24") (pintype "passive"))
      (node (ref "U6") (pin "4") (pinfunction "POL_4") (pintype "passive"))
      (node (ref "U6") (pin "8") (pinfunction "AGND_8") (pintype "passive"))
      (node (ref "U7") (pin "15") (pinfunction "REF_IN(-)_15") (pintype "passive"))
      (node (ref "U7") (pin "24") (pinfunction "DGND_24") (pintype "passive"))
      (node (ref "U7") (pin "4") (pinfunction "POL_4") (pintype "passive"))
      (node (ref "U7") (pin "8") (pinfunction "AGND_8") (pintype "passive"))
      (node (ref "U8") (pin "15") (pinfunction "REF_IN(-)_15") (pintype "passive"))
      (node (ref "U8") (pin "24") (pinfunction "DGND_24") (pintype "passive"))
      (node (ref "U8") (pin "4") (pinfunction "POL_4") (pintype "passive"))
      (node (ref "U8") (pin "8") (pinfunction "AGND_8") (pintype "passive"))
      (node (ref "U9") (pin "12") (pinfunction "VSSA_12") (pintype "passive"))
      (node (ref "U9") (pin "18") (pinfunction "VSS_4_18") (pintype "passive"))
      (node (ref "U9") (pin "31") (pinfunction "VSS_1_31") (pintype "passive"))
      (node (ref "U9") (pin "47") (pinfunction "VSS_2_47") (pintype "passive"))
      (node (ref "U9") (pin "63") (pinfunction "VSS_3_63") (pintype "passive"))
      (node (ref "Y1") (pin "2") (pinfunction "GND1_2") (pintype "bidirectional"))
      (node (ref "Y1") (pin "4") (pinfunction "GND2_4") (pintype "bidirectional"))
      (node (ref "Y2") (pin "2") (pinfunction "GND_2") (pintype "bidirectional"))
    )
    (net (code "74") (name "Net-(ID0-Pad1)") (class "Default")
      (node (ref "ID0") (pin "1") (pinfunction "1_1") (pintype "passive"))
      (node (ref "SV5") (pin "24") (pinfunction "24_24") (pintype "passive"))
    )
    (net (code "75") (name "Net-(ID1-Pad1)") (class "Default")
      (node (ref "ID1") (pin "1") (pinfunction "1_1") (pintype "passive"))
      (node (ref "SV5") (pin "26") (pinfunction "26_26") (pintype "passive"))
    )
    (net (code "76") (name "Net-(ID2-Pad1)") (class "Default")
      (node (ref "ID2") (pin "1") (pinfunction "1_1") (pintype "passive"))
      (node (ref "SV5") (pin "32") (pinfunction "32_32") (pintype "passive"))
    )
    (net (code "77") (name "Net-(ID3-Pad1)") (class "Default")
      (node (ref "ID3") (pin "1") (pinfunction "1_1") (pintype "passive"))
      (node (ref "SV5") (pin "36") (pinfunction "36_36") (pintype "passive"))
    )
    (net (code "78") (name "Net-(ID4-Pad1)") (class "Default")
      (node (ref "ID4") (pin "1") (pinfunction "1_1") (pintype "passive"))
      (node (ref "SV5") (pin "7") (pinfunction "7_7") (pintype "passive"))
    )
    (net (code "79") (name "Net-(ID5-Pad1)") (class "Default")
      (node (ref "ID5") (pin "1") (pinfunction "1_1") (pintype "passive"))
      (node (ref "SV5") (pin "11") (pinfunction "11_11") (pintype "passive"))
    )
    (net (code "80") (name "Net-(ID6-Pad1)") (class "Default")
      (node (ref "ID6") (pin "1") (pinfunction "1_1") (pintype "passive"))
      (node (ref "SV5") (pin "13") (pinfunction "13_13") (pintype "passive"))
    )
    (net (code "81") (name "Net-(ID7-Pad1)") (class "Default")
      (node (ref "ID7") (pin "1") (pinfunction "1_1") (pintype "passive"))
      (node (ref "SV5") (pin "15") (pinfunction "15_15") (pintype "passive"))
    )
    (net (code "82") (name "Net-(ID8-Pad1)") (class "Default")
      (node (ref "ID8") (pin "1") (pinfunction "1_1") (pintype "passive"))
      (node (ref "SV5") (pin "31") (pinfunction "31_31") (pintype "passive"))
    )
    (net (code "83") (name "Net-(ID9-Pad1)") (class "Default")
      (node (ref "ID9") (pin "1") (pinfunction "1_1") (pintype "passive"))
      (node (ref "SV5") (pin "33") (pinfunction "33_33") (pintype "passive"))
    )
    (net (code "84") (name "Net-(ID10-Pad1)") (class "Default")
      (node (ref "ID10") (pin "1") (pinfunction "1_1") (pintype "passive"))
      (node (ref "SV5") (pin "35") (pinfunction "35_35") (pintype "passive"))
    )
    (net (code "85") (name "Net-(ID11-Pad1)") (class "Default")
      (node (ref "ID11") (pin "1") (pinfunction "1_1") (pintype "passive"))
      (node (ref "SV5") (pin "37") (pinfunction "37_37") (pintype "passive"))
    )
    (net (code "86") (name "Net-(ID12-Pad1)") (class "Default")
      (node (ref "ID12") (pin "1") (pinfunction "1_1") (pintype "passive"))
      (node (ref "SV5") (pin "3") (pinfunction "3_3") (pintype "passive"))
    )
    (net (code "87") (name "Net-(ID13-Pad1)") (class "Default")
      (node (ref "ID13") (pin "1") (pinfunction "1_1") (pintype "passive"))
      (node (ref "SV5") (pin "5") (pinfunction "5_5") (pintype "passive"))
    )
    (net (code "88") (name "Net-(ID14-Pad1)") (class "Default")
      (node (ref "ID14") (pin "1") (pinfunction "1_1") (pintype "passive"))
      (node (ref "SV5") (pin "8") (pinfunction "8_8") (pintype "passive"))
    )
    (net (code "89") (name "Net-(ID15-Pad1)") (class "Default")
      (node (ref "ID15") (pin "1") (pinfunction "1_1") (pintype "passive"))
      (node (ref "SV5") (pin "10") (pinfunction "10_10") (pintype "passive"))
    )
    (net (code "90") (name "Net-(U9-PD0_OSC_IN)") (class "Default")
      (node (ref "C8") (pin "1") (pinfunction "1_1") (pintype "passive"))
      (node (ref "U9") (pin "5") (pinfunction "PD0_OSC_IN_5") (pintype "input"))
      (node (ref "Y1") (pin "1") (pinfunction "OSC1_1") (pintype "bidirectional"))
    )
    (net (code "91") (name "Net-(U9-PD1_OSC_OUT)") (class "Default")
      (node (ref "C7") (pin "1") (pinfunction "1_1") (pintype "passive"))
      (node (ref "U9") (pin "6") (pinfunction "PD1_OSC_OUT_6") (pintype "output"))
      (node (ref "Y1") (pin "3") (pinfunction "OSC2_3") (pintype "bidirectional"))
    )
    (net (code "92") (name "unconnected-(SV5-Pad1)") (class "Default")
      (node (ref "SV5") (pin "1") (pinfunction "1_1") (pintype "passive"))
    )
    (net (code "93") (name "unconnected-(SV5-Pad12)") (class "Default")
      (node (ref "SV5") (pin "12") (pinfunction "12_12") (pintype "passive"))
    )
    (net (code "94") (name "unconnected-(SV5-Pad16)") (class "Default")
      (node (ref "SV5") (pin "16") (pinfunction "16_16") (pintype "passive"))
    )
    (net (code "95") (name "unconnected-(SV5-Pad17)") (class "Default")
      (node (ref "SV5") (pin "17") (pinfunction "17_17") (pintype "passive"))
    )
    (net (code "96") (name "unconnected-(SV5-Pad22)") (class "Default")
      (node (ref "SV5") (pin "22") (pinfunction "22_22") (pintype "passive"))
    )
    (net (code "97") (name "unconnected-(SV5-Pad27)") (class "Default")
      (node (ref "SV5") (pin "27") (pinfunction "27_27") (pintype "passive"))
    )
    (net (code "98") (name "unconnected-(SV5-Pad28)") (class "Default")
      (node (ref "SV5") (pin "28") (pinfunction "28_28") (pintype "passive"))
    )
    (net (code "99") (name "unconnected-(SV5-Pad29)") (class "Default")
      (node (ref "SV5") (pin "29") (pinfunction "29_29") (pintype "passive"))
    )
    (net (code "100") (name "unconnected-(SV5-Pad38)") (class "Default")
      (node (ref "SV5") (pin "38") (pinfunction "38_38") (pintype "passive"))
    )
    (net (code "101") (name "unconnected-(SV5-Pad40)") (class "Default")
      (node (ref "SV5") (pin "40") (pinfunction "40_40") (pintype "passive"))
    )
    (net (code "102") (name "unconnected-(U1-*ACX-Pad17)") (class "Default")
      (node (ref "U1") (pin "17") (pinfunction "*ACX_17") (pintype "passive"))
    )
    (net (code "103") (name "unconnected-(U1-ACX-Pad16)") (class "Default")
      (node (ref "U1") (pin "16") (pinfunction "ACX_16") (pintype "passive"))
    )
    (net (code "104") (name "unconnected-(U1-VBIAS-Pad7)") (class "Default")
      (node (ref "U1") (pin "7") (pinfunction "VBIAS_7") (pintype "passive"))
    )
    (net (code "105") (name "unconnected-(U2-*ACX-Pad17)") (class "Default")
      (node (ref "U2") (pin "17") (pinfunction "*ACX_17") (pintype "passive"))
    )
    (net (code "106") (name "unconnected-(U2-ACX-Pad16)") (class "Default")
      (node (ref "U2") (pin "16") (pinfunction "ACX_16") (pintype "passive"))
    )
    (net (code "107") (name "unconnected-(U2-VBIAS-Pad7)") (class "Default")
      (node (ref "U2") (pin "7") (pinfunction "VBIAS_7") (pintype "passive"))
    )
    (net (code "108") (name "unconnected-(U3-*ACX-Pad17)") (class "Default")
      (node (ref "U3") (pin "17") (pinfunction "*ACX_17") (pintype "passive"))
    )
    (net (code "109") (name "unconnected-(U3-ACX-Pad16)") (class "Default")
      (node (ref "U3") (pin "16") (pinfunction "ACX_16") (pintype "passive"))
    )
    (net (code "110") (name "unconnected-(U3-VBIAS-Pad7)") (class "Default")
      (node (ref "U3") (pin "7") (pinfunction "VBIAS_7") (pintype "passive"))
    )
    (net (code "111") (name "unconnected-(U4-*ACX-Pad17)") (class "Default")
      (node (ref "U4") (pin "17") (pinfunction "*ACX_17") (pintype "passive"))
    )
    (net (code "112") (name "unconnected-(U4-ACX-Pad16)") (class "Default")
      (node (ref "U4") (pin "16") (pinfunction "ACX_16") (pintype "passive"))
    )
    (net (code "113") (name "unconnected-(U4-VBIAS-Pad7)") (class "Default")
      (node (ref "U4") (pin "7") (pinfunction "VBIAS_7") (pintype "passive"))
    )
    (net (code "114") (name "unconnected-(U5-*ACX-Pad17)") (class "Default")
      (node (ref "U5") (pin "17") (pinfunction "*ACX_17") (pintype "passive"))
    )
    (net (code "115") (name "unconnected-(U5-ACX-Pad16)") (class "Default")
      (node (ref "U5") (pin "16") (pinfunction "ACX_16") (pintype "passive"))
    )
    (net (code "116") (name "unconnected-(U5-VBIAS-Pad7)") (class "Default")
      (node (ref "U5") (pin "7") (pinfunction "VBIAS_7") (pintype "passive"))
    )
    (net (code "117") (name "unconnected-(U6-*ACX-Pad17)") (class "Default")
      (node (ref "U6") (pin "17") (pinfunction "*ACX_17") (pintype "passive"))
    )
    (net (code "118") (name "unconnected-(U6-ACX-Pad16)") (class "Default")
      (node (ref "U6") (pin "16") (pinfunction "ACX_16") (pintype "passive"))
    )
    (net (code "119") (name "unconnected-(U6-VBIAS-Pad7)") (class "Default")
      (node (ref "U6") (pin "7") (pinfunction "VBIAS_7") (pintype "passive"))
    )
    (net (code "120") (name "unconnected-(U7-*ACX-Pad17)") (class "Default")
      (node (ref "U7") (pin "17") (pinfunction "*ACX_17") (pintype "passive"))
    )
    (net (code "121") (name "unconnected-(U7-ACX-Pad16)") (class "Default")
      (node (ref "U7") (pin "16") (pinfunction "ACX_16") (pintype "passive"))
    )
    (net (code "122") (name "unconnected-(U7-VBIAS-Pad7)") (class "Default")
      (node (ref "U7") (pin "7") (pinfunction "VBIAS_7") (pintype "passive"))
    )
    (net (code "123") (name "unconnected-(U8-*ACX-Pad17)") (class "Default")
      (node (ref "U8") (pin "17") (pinfunction "*ACX_17") (pintype "passive"))
    )
    (net (code "124") (name "unconnected-(U8-ACX-Pad16)") (class "Default")
      (node (ref "U8") (pin "16") (pinfunction "ACX_16") (pintype "passive"))
    )
    (net (code "125") (name "unconnected-(U8-MCLK_OUT-Pad3)") (class "Default")
      (node (ref "U8") (pin "3") (pinfunction "MCLK_OUT_3") (pintype "passive"))
    )
    (net (code "126") (name "unconnected-(U8-VBIAS-Pad7)") (class "Default")
      (node (ref "U8") (pin "7") (pinfunction "VBIAS_7") (pintype "passive"))
    )
    (net (code "127") (name "unconnected-(U9-BOOT0-Pad60)") (class "Default")
      (node (ref "U9") (pin "60") (pinfunction "BOOT0_60") (pintype "passive"))
    )
    (net (code "128") (name "unconnected-(U9-PA0-WKUP-Pad14)") (class "Default")
      (node (ref "U9") (pin "14") (pinfunction "PA0-WKUP_14") (pintype "bidirectional"))
    )
    (net (code "129") (name "unconnected-(U9-PA1-Pad15)") (class "Default")
      (node (ref "U9") (pin "15") (pinfunction "PA1_15") (pintype "bidirectional"))
    )
    (net (code "130") (name "unconnected-(U9-PA2-Pad16)") (class "Default")
      (node (ref "U9") (pin "16") (pinfunction "PA2_16") (pintype "bidirectional"))
    )
    (net (code "131") (name "unconnected-(U9-PA3-Pad17)") (class "Default")
      (node (ref "U9") (pin "17") (pinfunction "PA3_17") (pintype "bidirectional"))
    )
    (net (code "132") (name "unconnected-(U9-PA4-Pad20)") (class "Default")
      (node (ref "U9") (pin "20") (pinfunction "PA4_20") (pintype "bidirectional"))
    )
    (net (code "133") (name "unconnected-(U9-PA8-Pad41)") (class "Default")
      (node (ref "U9") (pin "41") (pinfunction "PA8_41") (pintype "bidirectional"))
    )
    (net (code "134") (name "unconnected-(U9-PB0-Pad26)") (class "Default")
      (node (ref "U9") (pin "26") (pinfunction "PB0_26") (pintype "bidirectional"))
    )
    (net (code "135") (name "unconnected-(U9-PB1-Pad27)") (class "Default")
      (node (ref "U9") (pin "27") (pinfunction "PB1_27") (pintype "bidirectional"))
    )
    (net (code "136") (name "unconnected-(U9-PB1_2-Pad28)") (class "Default")
      (node (ref "U9") (pin "28") (pinfunction "PB1_2_28") (pintype "bidirectional"))
    )
    (net (code "137") (name "unconnected-(U9-PB6-Pad58)") (class "Default")
      (node (ref "U9") (pin "58") (pinfunction "PB6_58") (pintype "bidirectional"))
    )
    (net (code "138") (name "unconnected-(U9-PB8-Pad61)") (class "Default")
      (node (ref "U9") (pin "61") (pinfunction "PB8_61") (pintype "bidirectional"))
    )
    (net (code "139") (name "unconnected-(U9-PB9-Pad62)") (class "Default")
      (node (ref "U9") (pin "62") (pinfunction "PB9_62") (pintype "bidirectional"))
    )
    (net (code "140") (name "unconnected-(U9-PB10-Pad29)") (class "Default")
      (node (ref "U9") (pin "29") (pinfunction "PB10_29") (pintype "bidirectional"))
    )
    (net (code "141") (name "unconnected-(U9-PB11-Pad30)") (class "Default")
      (node (ref "U9") (pin "30") (pinfunction "PB11_30") (pintype "bidirectional"))
    )
    (net (code "142") (name "unconnected-(U9-PB12-Pad33)") (class "Default")
      (node (ref "U9") (pin "33") (pinfunction "PB12_33") (pintype "bidirectional"))
    )
    (net (code "143") (name "unconnected-(U9-PB13-Pad34)") (class "Default")
      (node (ref "U9") (pin "34") (pinfunction "PB13_34") (pintype "bidirectional"))
    )
    (net (code "144") (name "unconnected-(U9-PB14-Pad35)") (class "Default")
      (node (ref "U9") (pin "35") (pinfunction "PB14_35") (pintype "bidirectional"))
    )
    (net (code "145") (name "unconnected-(U9-PB15-Pad36)") (class "Default")
      (node (ref "U9") (pin "36") (pinfunction "PB15_36") (pintype "bidirectional"))
    )
    (net (code "146") (name "unconnected-(U9-PC4-Pad24)") (class "Default")
      (node (ref "U9") (pin "24") (pinfunction "PC4_24") (pintype "passive"))
    )
    (net (code "147") (name "unconnected-(U9-PC5-Pad25)") (class "Default")
      (node (ref "U9") (pin "25") (pinfunction "PC5_25") (pintype "bidirectional"))
    )
    (net (code "148") (name "unconnected-(U9-PC10-Pad51)") (class "Default")
      (node (ref "U9") (pin "51") (pinfunction "PC10_51") (pintype "bidirectional"))
    )
    (net (code "149") (name "unconnected-(U9-PC11-Pad52)") (class "Default")
      (node (ref "U9") (pin "52") (pinfunction "PC11_52") (pintype "bidirectional"))
    )
    (net (code "150") (name "unconnected-(U9-PC12-Pad53)") (class "Default")
      (node (ref "U9") (pin "53") (pinfunction "PC12_53") (pintype "bidirectional"))
    )
    (net (code "151") (name "unconnected-(U9-PC13-TAMPER-RTC-Pad2)") (class "Default")
      (node (ref "U9") (pin "2") (pinfunction "PC13-TAMPER-RTC_2") (pintype "input"))
    )
    (net (code "152") (name "unconnected-(U9-PC14-OSC32_IN-Pad3)") (class "Default")
      (node (ref "U9") (pin "3") (pinfunction "PC14-OSC32_IN_3") (pintype "input"))
    )
    (net (code "153") (name "unconnected-(U9-PC15-OSC32_OUT-Pad4)") (class "Default")
      (node (ref "U9") (pin "4") (pinfunction "PC15-OSC32_OUT_4") (pintype "output"))
    )
    (net (code "154") (name "unconnected-(U9-PD2-Pad54)") (class "Default")
      (node (ref "U9") (pin "54") (pinfunction "PD2_54") (pintype "bidirectional"))
    )
    (net (code "155") (name "unconnected-(Y2-EN-Pad1)") (class "Default")
      (node (ref "Y2") (pin "1") (pinfunction "EN_1") (pintype "bidirectional"))
    )
  )
)
